# 0301_LTC6820_chip.net
KiCad netlist of a schematic drawn in Altium Designer
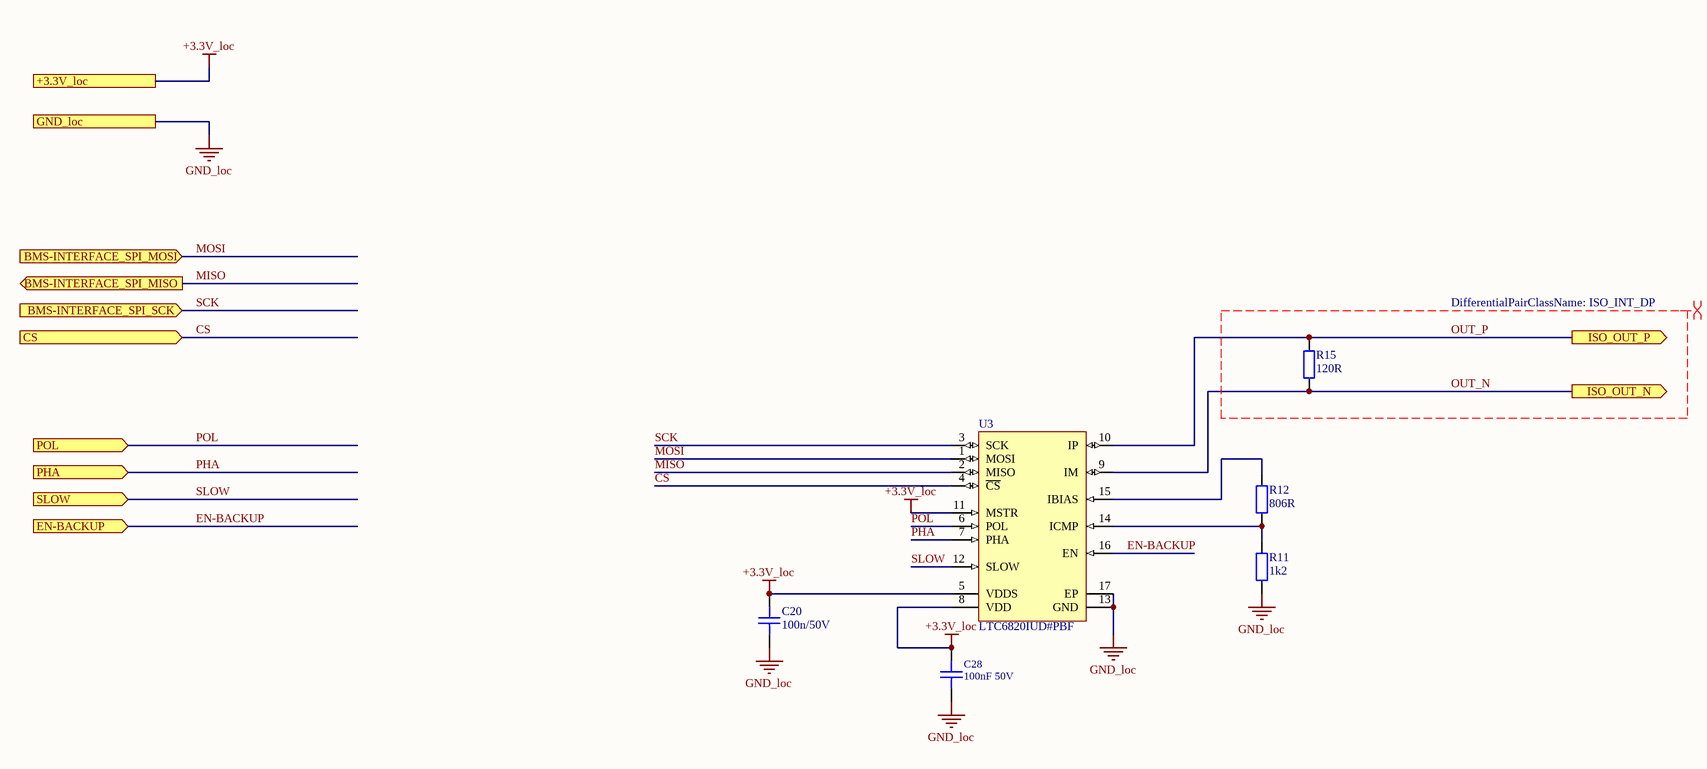
[diagram p0: 0301_LTC6820_chip.SchDoc]

(export (version "E")
  (design (tool "Eeschema 10.0.6"))
  (components
    (comp (ref "C20")
      (value "100n/50V")
      (footprint "0603C")
      (description "MLCC")
      (fields (field (name "PART NUMBER") "gen_C_ceramic_100n_50V_X7R_0603"))
      (libsource (lib "master-010106") (part "C"))
    )
    (comp (ref "C28")
      (value "100nF 50V")
      (footprint "0603C")
      (description "Ceramic, 100nF, ±10%, 50V, X7R, –55 to 125°C, 0603 (1608),RoHS, Automotive")
      (fields (field (name "PART NUMBER") "GCJ188R71H104KA12") (field (name "TOLERANCE") "±10%"))
      (libsource (lib "master-010106") (part "gen_C_ceramic_100n_50V_X7R_0603"))
    )
    (comp (ref "R11")
      (value "1k2")
      (footprint "0603R")
      (description "SMD Resistor 1k2 0603")
      (fields (field (name "PART NUMBER") "gen_R_1k2_0603") (field (name "TOLERANCE") "1%"))
      (libsource (lib "master-010106") (part "R"))
    )
    (comp (ref "R12")
      (value "806R")
      (footprint "0603R")
      (description "SMD Resistor 806R 0603")
      (fields (field (name "PART NUMBER") "gen_R_806R_0603") (field (name "TOLERANCE") "1%"))
      (libsource (lib "master-010106") (part "R"))
    )
    (comp (ref "R15")
      (value "120R")
      (footprint "0603R")
      (description "SMD Resistor 120R 0603")
      (fields (field (name "PART NUMBER") "gen_R_120R_0603") (field (name "TOLERANCE") "1%"))
      (libsource (lib "OE750") (part "R"))
    )
    (comp (ref "U3")
      (value "LTC6820IUD#PBF")
      (footprint "LT-UD-16-EPV-AA_L")
      (fields (field (name "MANUFACTURER") "Linear Technology"))
      (libsource (lib "Altium Content Vault") (part "LT-LTC6820-UD-16"))
    )
  )
  (nets
    (net (code "1") (name "+3.3V_loc") (class "Default")
      (node (ref "C20") (pin "2") (pinfunction "2_2") (pintype "passive"))
      (node (ref "C28") (pin "2") (pinfunction "2_2") (pintype "passive"))
      (node (ref "U3") (pin "11") (pinfunction "MSTR_11") (pintype "input"))
      (node (ref "U3") (pin "5") (pinfunction "VDDS_5") (pintype "power_in"))
      (node (ref "U3") (pin "8") (pinfunction "VDD_8") (pintype "power_in"))
    )
    (net (code "2") (name "/CS") (class "Default")
      (node (ref "U3") (pin "4") (pinfunction "~{CS}_4") (pintype "bidirectional"))
    )
    (net (code "3") (name "/EN-BACKUP") (class "Default")
      (node (ref "U3") (pin "16") (pinfunction "EN_16") (pintype "input"))
    )
    (net (code "4") (name "/MISO") (class "Default")
      (node (ref "U3") (pin "2") (pinfunction "MISO_2") (pintype "bidirectional"))
    )
    (net (code "5") (name "/MOSI") (class "Default")
      (node (ref "U3") (pin "1") (pinfunction "MOSI_1") (pintype "bidirectional"))
    )
    (net (code "6") (name "/OUT_N") (class "Default")
      (node (ref "R15") (pin "1") (pinfunction "1_1") (pintype "passive"))
      (node (ref "U3") (pin "9") (pinfunction "IM_9") (pintype "bidirectional"))
    )
    (net (code "7") (name "/OUT_P") (class "Default")
      (node (ref "R15") (pin "2") (pinfunction "2_2") (pintype "passive"))
      (node (ref "U3") (pin "10") (pinfunction "IP_10") (pintype "bidirectional"))
    )
    (net (code "8") (name "/PHA") (class "Default")
      (node (ref "U3") (pin "7") (pinfunction "PHA_7") (pintype "input"))
    )
    (net (code "9") (name "/POL") (class "Default")
      (node (ref "U3") (pin "6") (pinfunction "POL_6") (pintype "input"))
    )
    (net (code "10") (name "/SCK") (class "Default")
      (node (ref "U3") (pin "3") (pinfunction "SCK_3") (pintype "bidirectional"))
    )
    (net (code "11") (name "/SLOW") (class "Default")
      (node (ref "U3") (pin "12") (pinfunction "SLOW_12") (pintype "input"))
    )
    (net (code "12") (name "GND_loc") (class "Default")
      (node (ref "C20") (pin "1") (pinfunction "1_1") (pintype "passive"))
      (node (ref "C28") (pin "1") (pinfunction "1_1") (pintype "passive"))
      (node (ref "R11") (pin "1") (pinfunction "1_1") (pintype "passive"))
      (node (ref "U3") (pin "13") (pinfunction "GND_13") (pintype "power_in"))
      (node (ref "U3") (pin "17") (pinfunction "EP_17") (pintype "power_in"))
    )
    (net (code "13") (name "Net-(U3-IBIAS)") (class "Default")
      (node (ref "R12") (pin "2") (pinfunction "2_2") (pintype "passive"))
      (node (ref "U3") (pin "15") (pinfunction "IBIAS_15") (pintype "input"))
    )
    (net (code "14") (name "Net-(U3-ICMP)") (class "Default")
      (node (ref "R11") (pin "2") (pinfunction "2_2") (pintype "passive"))
      (node (ref "R12") (pin "1") (pinfunction "1_1") (pintype "passive"))
      (node (ref "U3") (pin "14") (pinfunction "ICMP_14") (pintype "input"))
    )
  )
)
